# CSX_Capsense.net
KiCad netlist of a schematic drawn in Altium Designer
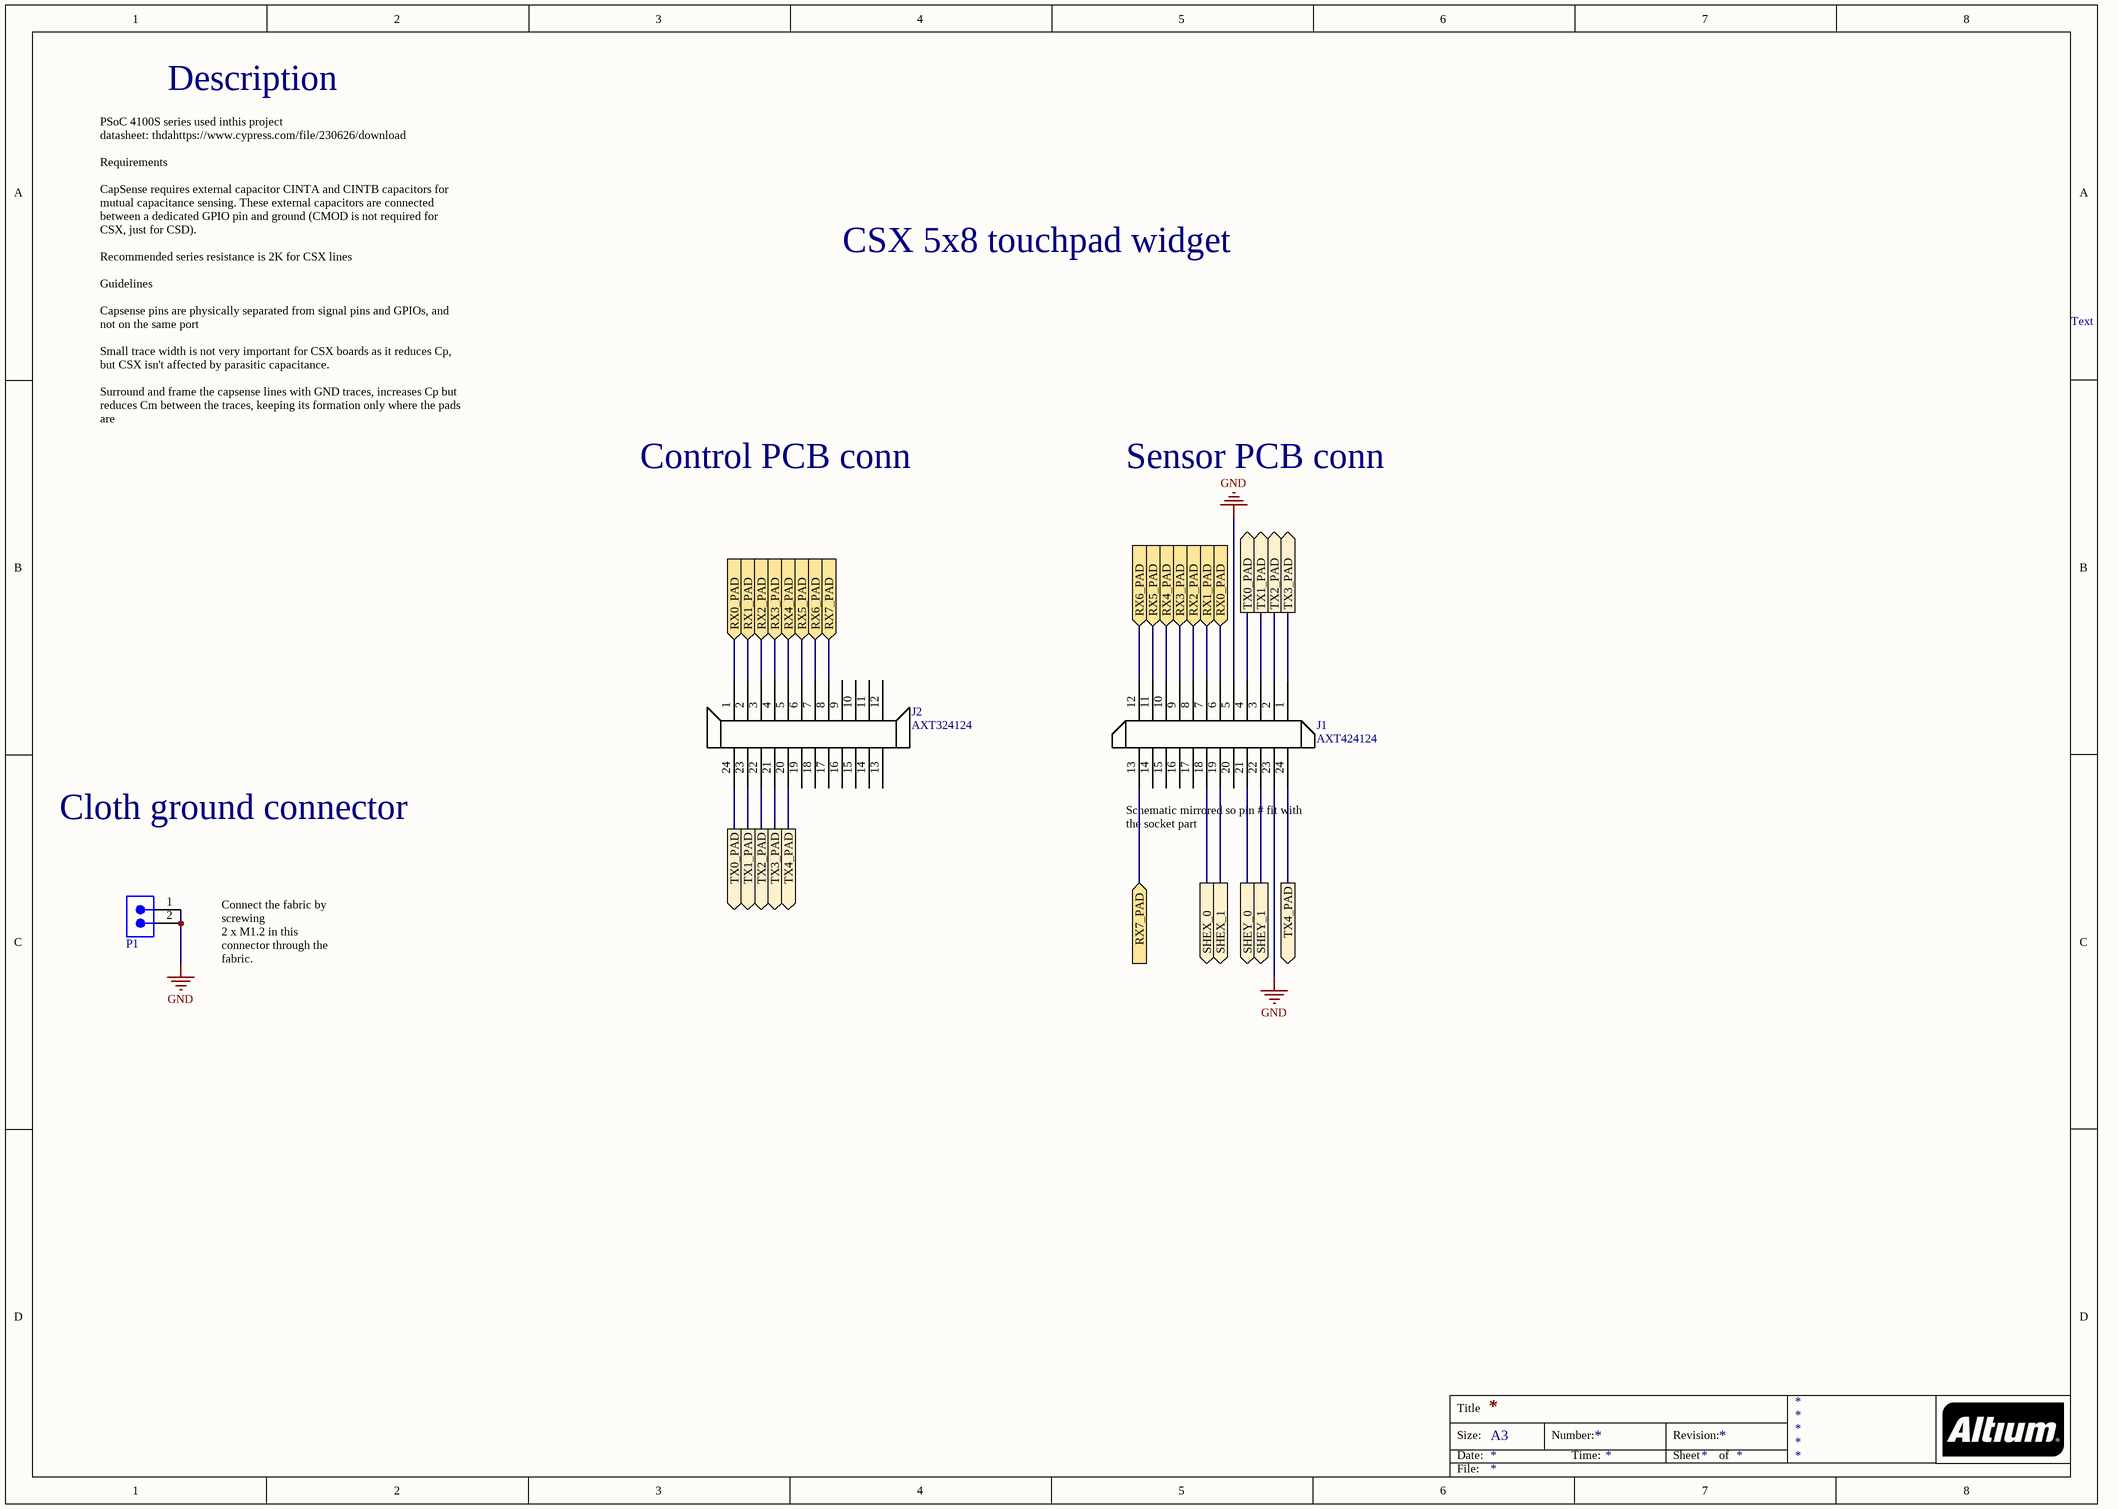
[diagram p0: CSX_Capsense.SchDoc]

(export (version "E")
  (design (tool "Eeschema 10.0.6"))
  (components
    (comp (ref "J1")
      (value "AXT424124")
      (footprint "AXT424124")
      (libsource (lib "customParts") (part "AXT424124"))
    )
    (comp (ref "J2")
      (value "AXT324124")
      (footprint "AXT324124")
      (libsource (lib "customParts") (part "AXT324124"))
    )
    (comp (ref "P1")
      (value "MTLW-102-05-T-S-172")
      (footprint "SMTC-MTLW-102-05-X-S-172")
      (fields (field (name "MANUFACTURER") "Samtec"))
      (libsource (lib "Altium Content Vault") (part "SMTC-MTLW-102-05-X-S-172"))
    )
  )
  (nets
    (net (code "1") (name "/RX0_PAD") (class "Default")
      (node (ref "J1") (pin "6") (pinfunction "6_6") (pintype "passive"))
      (node (ref "J2") (pin "1") (pinfunction "1_1") (pintype "passive"))
    )
    (net (code "2") (name "/RX1_PAD") (class "Default")
      (node (ref "J1") (pin "7") (pinfunction "7_7") (pintype "passive"))
      (node (ref "J2") (pin "2") (pinfunction "2_2") (pintype "passive"))
    )
    (net (code "3") (name "/RX2_PAD") (class "Default")
      (node (ref "J1") (pin "8") (pinfunction "8_8") (pintype "passive"))
      (node (ref "J2") (pin "3") (pinfunction "3_3") (pintype "passive"))
    )
    (net (code "4") (name "/RX3_PAD") (class "Default")
      (node (ref "J1") (pin "9") (pinfunction "9_9") (pintype "passive"))
      (node (ref "J2") (pin "4") (pinfunction "4_4") (pintype "passive"))
    )
    (net (code "5") (name "/RX4_PAD") (class "Default")
      (node (ref "J1") (pin "10") (pinfunction "10_10") (pintype "passive"))
      (node (ref "J2") (pin "5") (pinfunction "5_5") (pintype "passive"))
    )
    (net (code "6") (name "/RX5_PAD") (class "Default")
      (node (ref "J1") (pin "11") (pinfunction "11_11") (pintype "passive"))
      (node (ref "J2") (pin "6") (pinfunction "6_6") (pintype "passive"))
    )
    (net (code "7") (name "/RX6_PAD") (class "Default")
      (node (ref "J1") (pin "12") (pinfunction "12_12") (pintype "passive"))
      (node (ref "J2") (pin "7") (pinfunction "7_7") (pintype "passive"))
    )
    (net (code "8") (name "/RX7_PAD") (class "Default")
      (node (ref "J1") (pin "13") (pinfunction "13_13") (pintype "passive"))
      (node (ref "J2") (pin "8") (pinfunction "8_8") (pintype "passive"))
    )
    (net (code "9") (name "/SHEX_0") (class "Default")
      (node (ref "J1") (pin "18") (pinfunction "18_18") (pintype "passive"))
    )
    (net (code "10") (name "/SHEX_1") (class "Default")
      (node (ref "J1") (pin "19") (pinfunction "19_19") (pintype "passive"))
    )
    (net (code "11") (name "/SHEY_0") (class "Default")
      (node (ref "J1") (pin "21") (pinfunction "21_21") (pintype "passive"))
    )
    (net (code "12") (name "/SHEY_1") (class "Default")
      (node (ref "J1") (pin "22") (pinfunction "22_22") (pintype "passive"))
    )
    (net (code "13") (name "/TX0_PAD") (class "Default")
      (node (ref "J1") (pin "4") (pinfunction "4_4") (pintype "passive"))
      (node (ref "J2") (pin "24") (pinfunction "24_24") (pintype "passive"))
    )
    (net (code "14") (name "/TX1_PAD") (class "Default")
      (node (ref "J1") (pin "3") (pinfunction "3_3") (pintype "passive"))
      (node (ref "J2") (pin "23") (pinfunction "23_23") (pintype "passive"))
    )
    (net (code "15") (name "/TX2_PAD") (class "Default")
      (node (ref "J1") (pin "2") (pinfunction "2_2") (pintype "passive"))
      (node (ref "J2") (pin "22") (pinfunction "22_22") (pintype "passive"))
    )
    (net (code "16") (name "/TX3_PAD") (class "Default")
      (node (ref "J1") (pin "1") (pinfunction "1_1") (pintype "passive"))
      (node (ref "J2") (pin "21") (pinfunction "21_21") (pintype "passive"))
    )
    (net (code "17") (name "/TX4_PAD") (class "Default")
      (node (ref "J1") (pin "24") (pinfunction "24_24") (pintype "passive"))
      (node (ref "J2") (pin "20") (pinfunction "20_20") (pintype "passive"))
    )
    (net (code "18") (name "GND") (class "Default")
      (node (ref "J1") (pin "23") (pinfunction "23_23") (pintype "passive"))
      (node (ref "J1") (pin "5") (pinfunction "5_5") (pintype "passive"))
      (node (ref "P1") (pin "1") (pinfunction "1_1") (pintype "passive"))
      (node (ref "P1") (pin "2") (pinfunction "2_2") (pintype "passive"))
    )
    (net (code "19") (name "unconnected-(J1-Pad14)") (class "Default")
      (node (ref "J1") (pin "14") (pinfunction "14_14") (pintype "passive"))
    )
    (net (code "20") (name "unconnected-(J1-Pad15)") (class "Default")
      (node (ref "J1") (pin "15") (pinfunction "15_15") (pintype "passive"))
    )
    (net (code "21") (name "unconnected-(J1-Pad16)") (class "Default")
      (node (ref "J1") (pin "16") (pinfunction "16_16") (pintype "passive"))
    )
    (net (code "22") (name "unconnected-(J1-Pad17)") (class "Default")
      (node (ref "J1") (pin "17") (pinfunction "17_17") (pintype "passive"))
    )
    (net (code "23") (name "unconnected-(J1-Pad20)") (class "Default")
      (node (ref "J1") (pin "20") (pinfunction "20_20") (pintype "passive"))
    )
    (net (code "24") (name "unconnected-(J2-Pad9)") (class "Default")
      (node (ref "J2") (pin "9") (pinfunction "9_9") (pintype "passive"))
    )
    (net (code "25") (name "unconnected-(J2-Pad10)") (class "Default")
      (node (ref "J2") (pin "10") (pinfunction "10_10") (pintype "passive"))
    )
    (net (code "26") (name "unconnected-(J2-Pad11)") (class "Default")
      (node (ref "J2") (pin "11") (pinfunction "11_11") (pintype "passive"))
    )
    (net (code "27") (name "unconnected-(J2-Pad12)") (class "Default")
      (node (ref "J2") (pin "12") (pinfunction "12_12") (pintype "passive"))
    )
    (net (code "28") (name "unconnected-(J2-Pad13)") (class "Default")
      (node (ref "J2") (pin "13") (pinfunction "13_13") (pintype "passive"))
    )
    (net (code "29") (name "unconnected-(J2-Pad14)") (class "Default")
      (node (ref "J2") (pin "14") (pinfunction "14_14") (pintype "passive"))
    )
    (net (code "30") (name "unconnected-(J2-Pad15)") (class "Default")
      (node (ref "J2") (pin "15") (pinfunction "15_15") (pintype "passive"))
    )
    (net (code "31") (name "unconnected-(J2-Pad16)") (class "Default")
      (node (ref "J2") (pin "16") (pinfunction "16_16") (pintype "passive"))
    )
    (net (code "32") (name "unconnected-(J2-Pad17)") (class "Default")
      (node (ref "J2") (pin "17") (pinfunction "17_17") (pintype "passive"))
    )
    (net (code "33") (name "unconnected-(J2-Pad18)") (class "Default")
      (node (ref "J2") (pin "18") (pinfunction "18_18") (pintype "passive"))
    )
    (net (code "34") (name "unconnected-(J2-Pad19)") (class "Default")
      (node (ref "J2") (pin "19") (pinfunction "19_19") (pintype "passive"))
    )
  )
)
